# Board_with_LDC1614_no_ind_blink_V4.net
KiCad netlist of a schematic drawn in EAGLE
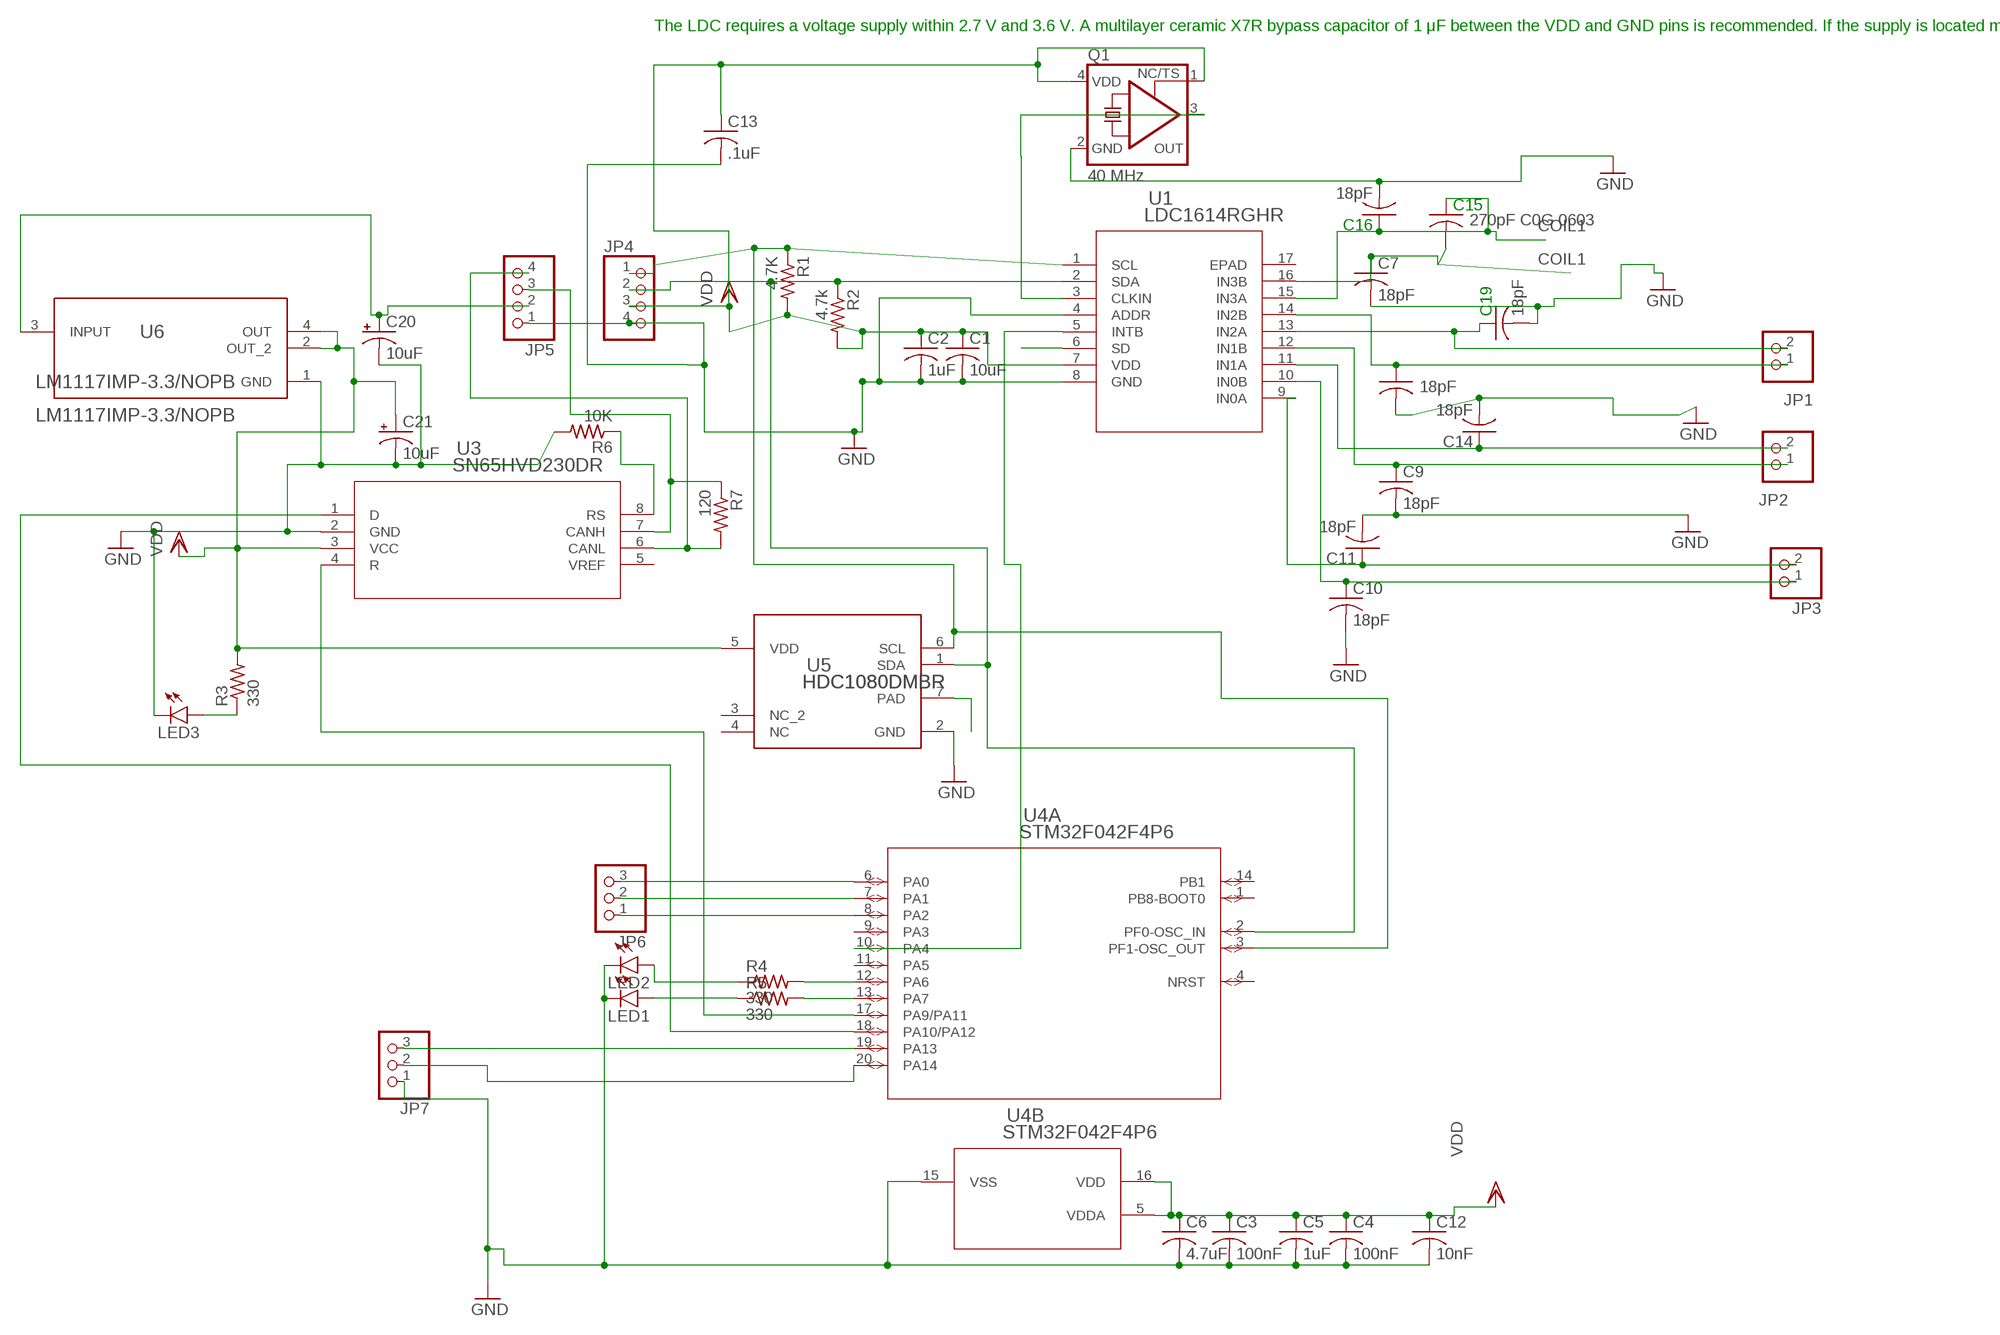
[diagram p0: schematic, sheet 1, part 1 of 2]
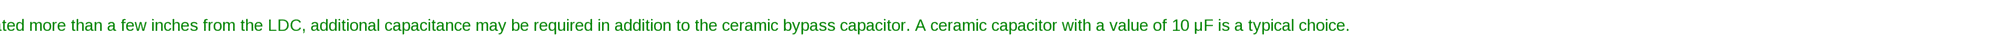
[diagram p1: schematic, sheet 1, part 2 of 2]

(export (version "E")
  (design (tool "Eeschema 10.0.6"))
  (components
    (comp (ref "C1")
      (value "10uF")
      (footprint "eagle-import:C0805")
      (libsource (lib "eagle-import") (part "C-USC0805"))
    )
    (comp (ref "C2")
      (value "1uF")
      (footprint "eagle-import:C0805")
      (libsource (lib "eagle-import") (part "C-USC0805"))
    )
    (comp (ref "C3")
      (value "100nF")
      (footprint "eagle-import:C0805")
      (libsource (lib "eagle-import") (part "C-USC0805"))
    )
    (comp (ref "C4")
      (value "100nF")
      (footprint "eagle-import:C0805")
      (libsource (lib "eagle-import") (part "C-USC0805"))
    )
    (comp (ref "C5")
      (value "1uF")
      (footprint "eagle-import:C0805")
      (libsource (lib "eagle-import") (part "C-USC0805"))
    )
    (comp (ref "C6")
      (value "4.7uF")
      (footprint "eagle-import:C0805")
      (libsource (lib "eagle-import") (part "C-USC0805"))
    )
    (comp (ref "C7")
      (value "18pF")
      (footprint "eagle-import:C0805")
      (libsource (lib "eagle-import") (part "C-USC0805"))
    )
    (comp (ref "C8")
      (value "18pF")
      (footprint "eagle-import:C0805")
      (libsource (lib "eagle-import") (part "C-USC0805"))
    )
    (comp (ref "C9")
      (value "18pF")
      (footprint "eagle-import:C0805")
      (libsource (lib "eagle-import") (part "C-USC0805"))
    )
    (comp (ref "C10")
      (value "18pF")
      (footprint "eagle-import:C0805")
      (libsource (lib "eagle-import") (part "C-USC0805"))
    )
    (comp (ref "C11")
      (value "18pF")
      (footprint "eagle-import:C0805")
      (libsource (lib "eagle-import") (part "C-USC0805"))
    )
    (comp (ref "C12")
      (value "10nF")
      (footprint "eagle-import:C0805")
      (libsource (lib "eagle-import") (part "C-USC0805"))
    )
    (comp (ref "C13")
      (value ".1uF")
      (footprint "eagle-import:C0805")
      (libsource (lib "eagle-import") (part "C-USC0805"))
    )
    (comp (ref "C14")
      (value "18pF")
      (footprint "eagle-import:C0805")
      (libsource (lib "eagle-import") (part "C-USC0805"))
    )
    (comp (ref "C15")
      (value "270pF C0G 0603")
      (footprint "eagle-import:C0805")
      (libsource (lib "eagle-import") (part "C-USC0805"))
    )
    (comp (ref "C16")
      (value "18pF")
      (footprint "eagle-import:C0805")
      (libsource (lib "eagle-import") (part "C-USC0805"))
    )
    (comp (ref "C19")
      (value "18pF")
      (footprint "eagle-import:C0805")
      (libsource (lib "eagle-import") (part "C-USC0805"))
    )
    (comp (ref "C20")
      (value "10uF")
      (footprint "eagle-import:A_3216-18R")
      (libsource (lib "eagle-import") (part "CPOL-USA/3216-18R"))
    )
    (comp (ref "C21")
      (value "10uF")
      (footprint "eagle-import:A_3216-18R")
      (libsource (lib "eagle-import") (part "CPOL-USA/3216-18R"))
    )
    (comp (ref "JP1")
      (value "PINHD-1X2/90")
      (footprint "eagle-import:1X02_90")
      (libsource (lib "eagle-import") (part "PINHD-1X2/90"))
    )
    (comp (ref "JP2")
      (value "PINHD-1X2/90")
      (footprint "eagle-import:1X02_90")
      (libsource (lib "eagle-import") (part "PINHD-1X2/90"))
    )
    (comp (ref "JP3")
      (value "PINHD-1X2/90")
      (footprint "eagle-import:1X02_90")
      (libsource (lib "eagle-import") (part "PINHD-1X2/90"))
    )
    (comp (ref "JP4")
      (value "PINHD-1X4/90")
      (footprint "eagle-import:1X04_90")
      (libsource (lib "eagle-import") (part "PINHD-1X4/90"))
    )
    (comp (ref "JP5")
      (value "PINHD-1X4/90")
      (footprint "eagle-import:1X04_90")
      (libsource (lib "eagle-import") (part "PINHD-1X4/90"))
    )
    (comp (ref "JP6")
      (value "PINHD-1X3")
      (footprint "eagle-import:1X03")
      (libsource (lib "eagle-import") (part "PINHD-1X3"))
    )
    (comp (ref "JP7")
      (value "PINHD-1X3")
      (footprint "eagle-import:1X03")
      (libsource (lib "eagle-import") (part "PINHD-1X3"))
    )
    (comp (ref "LED1")
      (value "LEDSML0603")
      (footprint "eagle-import:SML0603")
      (libsource (lib "eagle-import") (part "LEDSML0603"))
    )
    (comp (ref "LED2")
      (value "LEDSML0603")
      (footprint "eagle-import:SML0603")
      (libsource (lib "eagle-import") (part "LEDSML0603"))
    )
    (comp (ref "LED3")
      (value "LEDSML0603")
      (footprint "eagle-import:SML0603")
      (libsource (lib "eagle-import") (part "LEDSML0603"))
    )
    (comp (ref "Q1")
      (value "40 MHz")
      (footprint "eagle-import:2.5X2.0_KXO-V95")
      (fields (field (name "LCSC_PART") "C390542"))
      (libsource (lib "eagle-import") (part "KXO-PXO/XO-V95"))
    )
    (comp (ref "R1")
      (value "4.7K")
      (footprint "eagle-import:R0805")
      (libsource (lib "eagle-import") (part "R-US_R0805"))
    )
    (comp (ref "R2")
      (value "4.7k")
      (footprint "eagle-import:R0805")
      (libsource (lib "eagle-import") (part "R-US_R0805"))
    )
    (comp (ref "R3")
      (value "330")
      (footprint "eagle-import:R0603")
      (libsource (lib "eagle-import") (part "R-US_R0603"))
    )
    (comp (ref "R4")
      (value "330")
      (footprint "eagle-import:R0603")
      (libsource (lib "eagle-import") (part "R-US_R0603"))
    )
    (comp (ref "R5")
      (value "330")
      (footprint "eagle-import:R0603")
      (libsource (lib "eagle-import") (part "R-US_R0603"))
    )
    (comp (ref "R6")
      (value "10K")
      (footprint "eagle-import:R0603")
      (libsource (lib "eagle-import") (part "R-US_R0603"))
    )
    (comp (ref "R7")
      (value "120")
      (footprint "eagle-import:R0805")
      (libsource (lib "eagle-import") (part "R-US_R0805"))
    )
    (comp (ref "U1")
      (value "LDC1614RGHR")
      (footprint "eagle-import:RGH16_TEX")
      (fields (field (name "COPYRIGHT") "Copyright (C) 2022 Ultra Librarian. All rights reserved."))
      (libsource (lib "eagle-import") (part "LDC1614RGHR"))
    )
    (comp (ref "U3")
      (value "SN65HVD230DR")
      (footprint "eagle-import:D8")
      (fields (field (name "COPYRIGHT") "Copyright (C) 2022 Ultra Librarian. All rights reserved."))
      (libsource (lib "eagle-import") (part "SN65HVD230DR"))
    )
    (comp (ref "U4")
      (value "STM32F042F4P6")
      (footprint "eagle-import:TSSOP20")
      (fields (field (name "COPYRIGHT") "Copyright (C) 2022 Ultra Librarian. All rights reserved."))
      (libsource (lib "eagle-import") (part "STM32F042F4P6"))
    )
    (comp (ref "U5")
      (value "HDC1080DMBR")
      (footprint "eagle-import:DMB0006A")
      (fields (field (name "COPYRIGHT") "Copyright (C) 2022 Ultra Librarian. All rights reserved."))
      (libsource (lib "eagle-import") (part "HDC1080DMBR"))
    )
    (comp (ref "U6")
      (value "LM1117IMP-3.3/NOPB")
      (footprint "eagle-import:DCY0004A_N")
      (fields (field (name "COPYRIGHT") "Copyright (C) 2022 Ultra Librarian. All rights reserved."))
      (libsource (lib "eagle-import") (part "LM1117IMP-3.3/NOPB"))
    )
  )
  (nets
    (net (code "1") (name "/COIL1") (class "Default")
      (node (ref "C15") (pin "1") (pinfunction "1_1") (pintype "passive"))
      (node (ref "C15") (pin "2") (pinfunction "2_2") (pintype "passive"))
      (node (ref "C16") (pin "1") (pinfunction "1_1") (pintype "passive"))
      (node (ref "C7") (pin "1") (pinfunction "1_1") (pintype "passive"))
      (node (ref "U1") (pin "15") (pinfunction "IN3A_15") (pintype "input"))
      (node (ref "U1") (pin "16") (pinfunction "IN3B_16") (pintype "input"))
    )
    (net (code "2") (name "/VREF") (class "Default")
      (node (ref "U3") (pin "5") (pinfunction "VREF_5") (pintype "power_in"))
    )
    (net (code "3") (name "GND") (class "Default")
      (node (ref "C1") (pin "2") (pinfunction "2_2") (pintype "passive"))
      (node (ref "C10") (pin "2") (pinfunction "2_2") (pintype "passive"))
      (node (ref "C11") (pin "2") (pinfunction "2_2") (pintype "passive"))
      (node (ref "C12") (pin "2") (pinfunction "2_2") (pintype "passive"))
      (node (ref "C13") (pin "2") (pinfunction "2_2") (pintype "passive"))
      (node (ref "C14") (pin "2") (pinfunction "2_2") (pintype "passive"))
      (node (ref "C16") (pin "2") (pinfunction "2_2") (pintype "passive"))
      (node (ref "C19") (pin "2") (pinfunction "2_2") (pintype "passive"))
      (node (ref "C2") (pin "2") (pinfunction "2_2") (pintype "passive"))
      (node (ref "C20") (pin "-") (pinfunction "-_-") (pintype "passive"))
      (node (ref "C21") (pin "-") (pinfunction "-_-") (pintype "passive"))
      (node (ref "C3") (pin "2") (pinfunction "2_2") (pintype "passive"))
      (node (ref "C4") (pin "2") (pinfunction "2_2") (pintype "passive"))
      (node (ref "C5") (pin "2") (pinfunction "2_2") (pintype "passive"))
      (node (ref "C6") (pin "2") (pinfunction "2_2") (pintype "passive"))
      (node (ref "C7") (pin "2") (pinfunction "2_2") (pintype "passive"))
      (node (ref "C8") (pin "2") (pinfunction "2_2") (pintype "passive"))
      (node (ref "C9") (pin "2") (pinfunction "2_2") (pintype "passive"))
      (node (ref "JP4") (pin "4") (pinfunction "4_4") (pintype "passive"))
      (node (ref "JP5") (pin "1") (pinfunction "1_1") (pintype "passive"))
      (node (ref "JP7") (pin "1") (pinfunction "1_1") (pintype "passive"))
      (node (ref "LED1") (pin "C") (pinfunction "C_C") (pintype "passive"))
      (node (ref "LED2") (pin "C") (pinfunction "C_C") (pintype "passive"))
      (node (ref "LED3") (pin "C") (pinfunction "C_C") (pintype "passive"))
      (node (ref "Q1") (pin "2") (pinfunction "GND_2") (pintype "power_in"))
      (node (ref "R6") (pin "2") (pinfunction "2_2") (pintype "passive"))
      (node (ref "U1") (pin "4") (pinfunction "ADDR_4") (pintype "input"))
      (node (ref "U1") (pin "8") (pinfunction "GND_8") (pintype "power_in"))
      (node (ref "U3") (pin "2") (pinfunction "GND_2") (pintype "power_in"))
      (node (ref "U4") (pin "15") (pinfunction "VSS_15") (pintype "power_in"))
      (node (ref "U5") (pin "2") (pinfunction "GND_2") (pintype "power_in"))
      (node (ref "U6") (pin "1") (pinfunction "GND_1") (pintype "power_in"))
    )
    (net (code "4") (name "Net-(LED1-PadA)") (class "Default")
      (node (ref "LED1") (pin "A") (pinfunction "A_A") (pintype "passive"))
      (node (ref "R5") (pin "1") (pinfunction "1_1") (pintype "passive"))
    )
    (net (code "5") (name "Net-(LED2-PadA)") (class "Default")
      (node (ref "LED2") (pin "A") (pinfunction "A_A") (pintype "passive"))
      (node (ref "R4") (pin "1") (pinfunction "1_1") (pintype "passive"))
    )
    (net (code "6") (name "Net-(LED3-PadA)") (class "Default")
      (node (ref "LED3") (pin "A") (pinfunction "A_A") (pintype "passive"))
      (node (ref "R3") (pin "1") (pinfunction "1_1") (pintype "passive"))
    )
    (net (code "7") (name "Net-(Q1-OUT)") (class "Default")
      (node (ref "Q1") (pin "3") (pinfunction "OUT_3") (pintype "output"))
      (node (ref "U1") (pin "3") (pinfunction "CLKIN_3") (pintype "input"))
    )
    (net (code "8") (name "Net-(U1-IN0A)") (class "Default")
      (node (ref "C11") (pin "1") (pinfunction "1_1") (pintype "passive"))
      (node (ref "JP3") (pin "2") (pinfunction "2_2") (pintype "passive"))
      (node (ref "U1") (pin "9") (pinfunction "IN0A_9") (pintype "input"))
    )
    (net (code "9") (name "Net-(U1-IN0B)") (class "Default")
      (node (ref "C10") (pin "1") (pinfunction "1_1") (pintype "passive"))
      (node (ref "JP3") (pin "1") (pinfunction "1_1") (pintype "passive"))
      (node (ref "U1") (pin "10") (pinfunction "IN0B_10") (pintype "input"))
    )
    (net (code "10") (name "Net-(U1-IN1A)") (class "Default")
      (node (ref "C14") (pin "1") (pinfunction "1_1") (pintype "passive"))
      (node (ref "JP2") (pin "2") (pinfunction "2_2") (pintype "passive"))
      (node (ref "U1") (pin "11") (pinfunction "IN1A_11") (pintype "input"))
    )
    (net (code "11") (name "Net-(U1-IN1B)") (class "Default")
      (node (ref "C9") (pin "1") (pinfunction "1_1") (pintype "passive"))
      (node (ref "JP2") (pin "1") (pinfunction "1_1") (pintype "passive"))
      (node (ref "U1") (pin "12") (pinfunction "IN1B_12") (pintype "input"))
    )
    (net (code "12") (name "Net-(U1-IN2A)") (class "Default")
      (node (ref "C19") (pin "1") (pinfunction "1_1") (pintype "passive"))
      (node (ref "JP1") (pin "2") (pinfunction "2_2") (pintype "passive"))
      (node (ref "U1") (pin "13") (pinfunction "IN2A_13") (pintype "input"))
    )
    (net (code "13") (name "Net-(U1-IN2B)") (class "Default")
      (node (ref "C8") (pin "1") (pinfunction "1_1") (pintype "passive"))
      (node (ref "JP1") (pin "1") (pinfunction "1_1") (pintype "passive"))
      (node (ref "U1") (pin "14") (pinfunction "IN2B_14") (pintype "input"))
    )
    (net (code "14") (name "Net-(U1-INTB)") (class "Default")
      (node (ref "U1") (pin "5") (pinfunction "INTB_5") (pintype "output"))
      (node (ref "U4") (pin "10") (pinfunction "PA4_10") (pintype "bidirectional"))
    )
    (net (code "15") (name "Net-(U1-SCL)") (class "Default")
      (node (ref "JP4") (pin "1") (pinfunction "1_1") (pintype "passive"))
      (node (ref "R1") (pin "1") (pinfunction "1_1") (pintype "passive"))
      (node (ref "U1") (pin "1") (pinfunction "SCL_1") (pintype "input"))
      (node (ref "U4") (pin "3") (pinfunction "PF1-OSC_OUT_3") (pintype "bidirectional"))
      (node (ref "U5") (pin "6") (pinfunction "SCL_6") (pintype "open_collector"))
    )
    (net (code "16") (name "Net-(U1-SDA)") (class "Default")
      (node (ref "JP4") (pin "2") (pinfunction "2_2") (pintype "passive"))
      (node (ref "R2") (pin "1") (pinfunction "1_1") (pintype "passive"))
      (node (ref "U1") (pin "2") (pinfunction "SDA_2") (pintype "bidirectional"))
      (node (ref "U4") (pin "2") (pinfunction "PF0-OSC_IN_2") (pintype "bidirectional"))
      (node (ref "U5") (pin "1") (pinfunction "SDA_1") (pintype "bidirectional"))
    )
    (net (code "17") (name "Net-(U3-CANH)") (class "Default")
      (node (ref "JP5") (pin "3") (pinfunction "3_3") (pintype "passive"))
      (node (ref "R7") (pin "1") (pinfunction "1_1") (pintype "passive"))
      (node (ref "U3") (pin "7") (pinfunction "CANH_7") (pintype "output"))
    )
    (net (code "18") (name "Net-(U3-CANL)") (class "Default")
      (node (ref "JP5") (pin "4") (pinfunction "4_4") (pintype "passive"))
      (node (ref "R7") (pin "2") (pinfunction "2_2") (pintype "passive"))
      (node (ref "U3") (pin "6") (pinfunction "CANL_6") (pintype "output"))
    )
    (net (code "19") (name "Net-(U3-D)") (class "Default")
      (node (ref "U3") (pin "1") (pinfunction "D_1") (pintype "input"))
      (node (ref "U4") (pin "18") (pinfunction "PA10/PA12_18") (pintype "bidirectional"))
    )
    (net (code "20") (name "Net-(U3-R)") (class "Default")
      (node (ref "U3") (pin "4") (pinfunction "R_4") (pintype "input"))
      (node (ref "U4") (pin "17") (pinfunction "PA9/PA11_17") (pintype "bidirectional"))
    )
    (net (code "21") (name "Net-(U3-RS)") (class "Default")
      (node (ref "R6") (pin "1") (pinfunction "1_1") (pintype "passive"))
      (node (ref "U3") (pin "8") (pinfunction "RS_8") (pintype "input"))
    )
    (net (code "22") (name "Net-(U4A-PA0)") (class "Default")
      (node (ref "JP6") (pin "3") (pinfunction "3_3") (pintype "passive"))
      (node (ref "U4") (pin "6") (pinfunction "PA0_6") (pintype "bidirectional"))
    )
    (net (code "23") (name "Net-(U4A-PA1)") (class "Default")
      (node (ref "JP6") (pin "2") (pinfunction "2_2") (pintype "passive"))
      (node (ref "U4") (pin "7") (pinfunction "PA1_7") (pintype "bidirectional"))
    )
    (net (code "24") (name "Net-(U4A-PA2)") (class "Default")
      (node (ref "JP6") (pin "1") (pinfunction "1_1") (pintype "passive"))
      (node (ref "U4") (pin "8") (pinfunction "PA2_8") (pintype "bidirectional"))
    )
    (net (code "25") (name "Net-(U4A-PA6)") (class "Default")
      (node (ref "R4") (pin "2") (pinfunction "2_2") (pintype "passive"))
      (node (ref "U4") (pin "12") (pinfunction "PA6_12") (pintype "bidirectional"))
    )
    (net (code "26") (name "Net-(U4A-PA7)") (class "Default")
      (node (ref "R5") (pin "2") (pinfunction "2_2") (pintype "passive"))
      (node (ref "U4") (pin "13") (pinfunction "PA7_13") (pintype "bidirectional"))
    )
    (net (code "27") (name "Net-(U4A-PA13)") (class "Default")
      (node (ref "JP7") (pin "3") (pinfunction "3_3") (pintype "passive"))
      (node (ref "U4") (pin "19") (pinfunction "PA13_19") (pintype "bidirectional"))
    )
    (net (code "28") (name "Net-(U4A-PA14)") (class "Default")
      (node (ref "JP7") (pin "2") (pinfunction "2_2") (pintype "passive"))
      (node (ref "U4") (pin "20") (pinfunction "PA14_20") (pintype "bidirectional"))
    )
    (net (code "29") (name "Net-(U6-INPUT)") (class "Default")
      (node (ref "C20") (pin "+") (pinfunction "+_+") (pintype "passive"))
      (node (ref "JP5") (pin "2") (pinfunction "2_2") (pintype "passive"))
      (node (ref "U6") (pin "3") (pinfunction "INPUT_3") (pintype "power_in"))
    )
    (net (code "30") (name "VDD") (class "Default")
      (node (ref "C1") (pin "1") (pinfunction "1_1") (pintype "passive"))
      (node (ref "C12") (pin "1") (pinfunction "1_1") (pintype "passive"))
      (node (ref "C13") (pin "1") (pinfunction "1_1") (pintype "passive"))
      (node (ref "C2") (pin "1") (pinfunction "1_1") (pintype "passive"))
      (node (ref "C21") (pin "+") (pinfunction "+_+") (pintype "passive"))
      (node (ref "C3") (pin "1") (pinfunction "1_1") (pintype "passive"))
      (node (ref "C4") (pin "1") (pinfunction "1_1") (pintype "passive"))
      (node (ref "C5") (pin "1") (pinfunction "1_1") (pintype "passive"))
      (node (ref "C6") (pin "1") (pinfunction "1_1") (pintype "passive"))
      (node (ref "JP4") (pin "3") (pinfunction "3_3") (pintype "passive"))
      (node (ref "Q1") (pin "1") (pinfunction "TS_1") (pintype "passive"))
      (node (ref "Q1") (pin "4") (pinfunction "VDD_4") (pintype "power_in"))
      (node (ref "R1") (pin "2") (pinfunction "2_2") (pintype "passive"))
      (node (ref "R2") (pin "2") (pinfunction "2_2") (pintype "passive"))
      (node (ref "R3") (pin "2") (pinfunction "2_2") (pintype "passive"))
      (node (ref "U1") (pin "7") (pinfunction "VDD_7") (pintype "power_in"))
      (node (ref "U3") (pin "3") (pinfunction "VCC_3") (pintype "power_in"))
      (node (ref "U4") (pin "16") (pinfunction "VDD_16") (pintype "power_in"))
      (node (ref "U4") (pin "5") (pinfunction "VDDA_5") (pintype "power_in"))
      (node (ref "U5") (pin "5") (pinfunction "VDD_5") (pintype "power_in"))
      (node (ref "U6") (pin "2") (pinfunction "OUT_2_2") (pintype "power_in"))
      (node (ref "U6") (pin "4") (pinfunction "OUT_4") (pintype "power_in"))
    )
    (net (code "31") (name "unconnected-(U1-EPAD-Pad17)") (class "Default")
      (node (ref "U1") (pin "17") (pinfunction "EPAD_17") (pintype "passive"))
    )
    (net (code "32") (name "unconnected-(U1-SD-Pad6)") (class "Default")
      (node (ref "U1") (pin "6") (pinfunction "SD_6") (pintype "input"))
    )
    (net (code "33") (name "unconnected-(U4A-NRST-Pad4)") (class "Default")
      (node (ref "U4") (pin "4") (pinfunction "NRST_4") (pintype "bidirectional"))
    )
    (net (code "34") (name "unconnected-(U4A-PA3-Pad9)") (class "Default")
      (node (ref "U4") (pin "9") (pinfunction "PA3_9") (pintype "bidirectional"))
    )
    (net (code "35") (name "unconnected-(U4A-PA5-Pad11)") (class "Default")
      (node (ref "U4") (pin "11") (pinfunction "PA5_11") (pintype "bidirectional"))
    )
    (net (code "36") (name "unconnected-(U4A-PB1-Pad14)") (class "Default")
      (node (ref "U4") (pin "14") (pinfunction "PB1_14") (pintype "bidirectional"))
    )
    (net (code "37") (name "unconnected-(U4A-PB8-BOOT0-Pad1)") (class "Default")
      (node (ref "U4") (pin "1") (pinfunction "PB8-BOOT0_1") (pintype "bidirectional"))
    )
    (net (code "38") (name "unconnected-(U5-NC-Pad4)") (class "Default")
      (node (ref "U5") (pin "4") (pinfunction "NC_4") (pintype "passive"))
    )
    (net (code "39") (name "unconnected-(U5-NC_2-Pad3)") (class "Default")
      (node (ref "U5") (pin "3") (pinfunction "NC_2_3") (pintype "passive"))
    )
    (net (code "40") (name "unconnected-(U5-PAD-Pad7)") (class "Default")
      (node (ref "U5") (pin "7") (pinfunction "PAD_7") (pintype "power_in"))
    )
  )
)
